# QCopterMV_PWM_Sch.net
KiCad netlist of a schematic drawn in Altium Designer
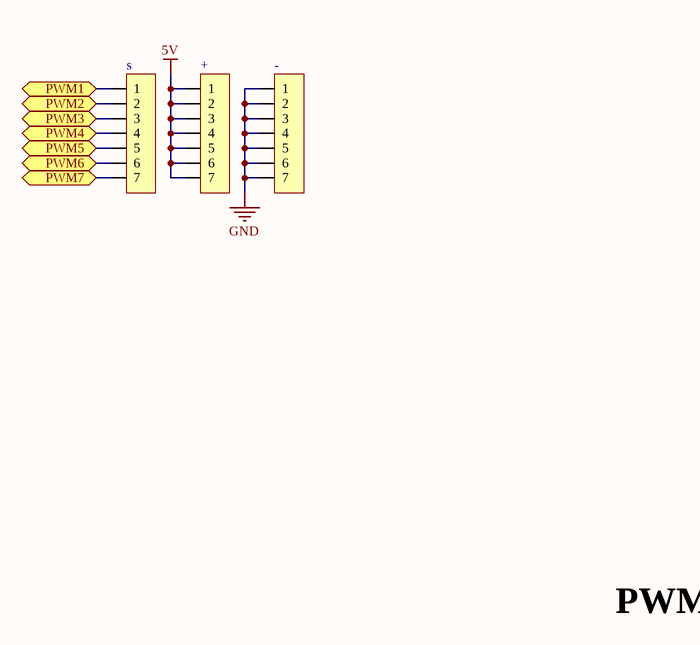
[diagram p0: QCopterMV_PWM_Sch.SchDoc]

(export (version "E")
  (design (tool "Eeschema 10.0.6"))
  (components
    (comp (ref "+")
      (value "HDR1X7_180_2.54")
      (footprint "PCB_Connector:HDR1X7_180_2.54")
      (description "Header")
      (libsource (lib "SCH_Connector") (part "HDR1X7_180_2.54"))
    )
    (comp (ref "-")
      (value "HDR1X7_180_2.54")
      (footprint "PCB_Connector:HDR1X7_180_2.54")
      (description "Header")
      (libsource (lib "SCH_Connector") (part "HDR1X7_180_2.54"))
    )
    (comp (ref "s")
      (value "HDR1X7_180_2.54")
      (footprint "PCB_Connector:HDR1X7_180_2.54")
      (description "Header")
      (libsource (lib "SCH_Connector") (part "HDR1X7_180_2.54"))
    )
  )
  (nets
    (net (code "1") (name "/PWM1") (class "Default")
      (node (ref "s") (pin "1") (pinfunction "1_1") (pintype "passive"))
    )
    (net (code "2") (name "/PWM2") (class "Default")
      (node (ref "s") (pin "2") (pinfunction "2_2") (pintype "passive"))
    )
    (net (code "3") (name "/PWM3") (class "Default")
      (node (ref "s") (pin "3") (pinfunction "3_3") (pintype "passive"))
    )
    (net (code "4") (name "/PWM4") (class "Default")
      (node (ref "s") (pin "4") (pinfunction "4_4") (pintype "passive"))
    )
    (net (code "5") (name "/PWM5") (class "Default")
      (node (ref "s") (pin "5") (pinfunction "5_5") (pintype "passive"))
    )
    (net (code "6") (name "/PWM6") (class "Default")
      (node (ref "s") (pin "6") (pinfunction "6_6") (pintype "passive"))
    )
    (net (code "7") (name "/PWM7") (class "Default")
      (node (ref "s") (pin "7") (pinfunction "7_7") (pintype "passive"))
    )
    (net (code "8") (name "5V") (class "Default")
      (node (ref "+") (pin "1") (pinfunction "1_1") (pintype "passive"))
      (node (ref "+") (pin "2") (pinfunction "2_2") (pintype "passive"))
      (node (ref "+") (pin "3") (pinfunction "3_3") (pintype "passive"))
      (node (ref "+") (pin "4") (pinfunction "4_4") (pintype "passive"))
      (node (ref "+") (pin "5") (pinfunction "5_5") (pintype "passive"))
      (node (ref "+") (pin "6") (pinfunction "6_6") (pintype "passive"))
      (node (ref "+") (pin "7") (pinfunction "7_7") (pintype "passive"))
    )
    (net (code "9") (name "GND") (class "Default")
      (node (ref "-") (pin "1") (pinfunction "1_1") (pintype "passive"))
      (node (ref "-") (pin "2") (pinfunction "2_2") (pintype "passive"))
      (node (ref "-") (pin "3") (pinfunction "3_3") (pintype "passive"))
      (node (ref "-") (pin "4") (pinfunction "4_4") (pintype "passive"))
      (node (ref "-") (pin "5") (pinfunction "5_5") (pintype "passive"))
      (node (ref "-") (pin "6") (pinfunction "6_6") (pintype "passive"))
      (node (ref "-") (pin "7") (pinfunction "7_7") (pintype "passive"))
    )
  )
)
